# External_Flash.net
KiCad netlist of a schematic drawn in Altium Designer
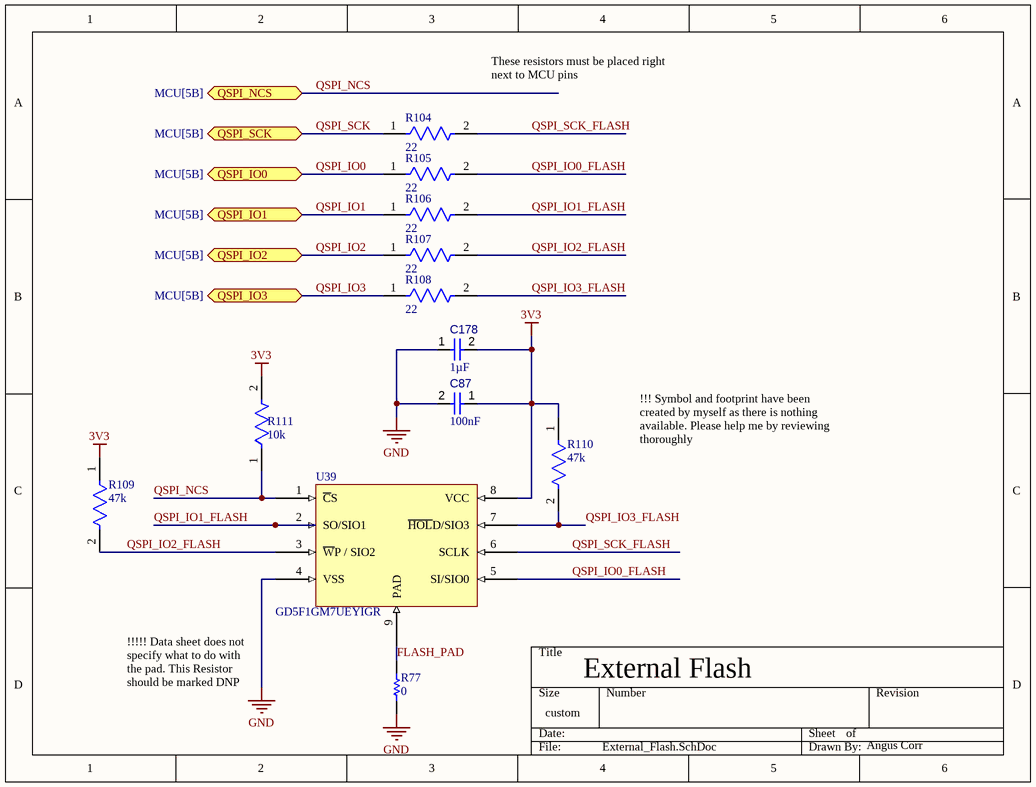
[diagram p0:  External_Flash.SchDoc]

(export (version "E")
  (design (tool "Eeschema 10.0.6"))
  (components
    (comp (ref "C87")
      (value "100nF")
      (footprint "CAPC1608X90X40NL10T20")
      (description "Chip Capacitor, 100 nF, +/- 10%, 50 V, 0603 (1608 Metric)")
      (fields (field (name "TOLERANCE") "10%") (field (name "Comment") "Capacitor 100 nF +/-10% 50 V 0603"))
      (libsource (lib "HIL RIG FYP") (part "CAP-NP-2"))
    )
    (comp (ref "C178")
      (value "1µF")
      (footprint "CAPC1608X90X40LL10T20")
      (description "Chip Capacitor, 1 uF, +/- 10%, 25 V, 0603 (1608 Metric)")
      (fields (field (name "TOLERANCE") "10%") (field (name "Comment") "Capacitor 1 uF +/- 10% 25 V 0603"))
      (libsource (lib "HIL RIG FYP") (part "CAP-NP-2"))
    )
    (comp (ref "R77")
      (value "0")
      (footprint "RESC1608X55X25ML10T15")
      (description "Chip Resistor, 0 Ohm, 0.1 W, -55 to 155 degC, 0603 (1608 Metric)")
      (fields (field (name "POWER") "100mW") (field (name "TOLERANCE") "5%"))
      (libsource (lib "HIL RIG FYP") (part "RES-2"))
    )
    (comp (ref "R104")
      (value "22")
      (footprint "FP-RC0603-0_55-IPC_A")
      (description "100mW Thick Film Resistors 75V ±100ppm/℃ ±5% 22Ω 0603 Chip Resistor - Surface Mount ROHS")
      (fields (field (name "TOLERANCE") "5%") (field (name "Comment") "RC0603JR-0722RL"))
      (libsource (lib "HIL RIG FYP") (part "1029c3af85768c4190bb7ad29bc67b5"))
    )
    (comp (ref "R105")
      (value "22")
      (footprint "FP-RC0603-0_55-IPC_A")
      (description "100mW Thick Film Resistors 75V ±100ppm/℃ ±5% 22Ω 0603 Chip Resistor - Surface Mount ROHS")
      (fields (field (name "TOLERANCE") "5%") (field (name "Comment") "RC0603JR-0722RL"))
      (libsource (lib "HIL RIG FYP") (part "1029c3af85768c4190bb7ad29bc67b5"))
    )
    (comp (ref "R106")
      (value "22")
      (footprint "FP-RC0603-0_55-IPC_A")
      (description "100mW Thick Film Resistors 75V ±100ppm/℃ ±5% 22Ω 0603 Chip Resistor - Surface Mount ROHS")
      (fields (field (name "TOLERANCE") "5%") (field (name "Comment") "RC0603JR-0722RL"))
      (libsource (lib "HIL RIG FYP") (part "1029c3af85768c4190bb7ad29bc67b5"))
    )
    (comp (ref "R107")
      (value "22")
      (footprint "FP-RC0603-0_55-IPC_A")
      (description "100mW Thick Film Resistors 75V ±100ppm/℃ ±5% 22Ω 0603 Chip Resistor - Surface Mount ROHS")
      (fields (field (name "TOLERANCE") "5%") (field (name "Comment") "RC0603JR-0722RL"))
      (libsource (lib "HIL RIG FYP") (part "1029c3af85768c4190bb7ad29bc67b5"))
    )
    (comp (ref "R108")
      (value "22")
      (footprint "FP-RC0603-0_55-IPC_A")
      (description "100mW Thick Film Resistors 75V ±100ppm/℃ ±5% 22Ω 0603 Chip Resistor - Surface Mount ROHS")
      (fields (field (name "TOLERANCE") "5%") (field (name "Comment") "RC0603JR-0722RL"))
      (libsource (lib "HIL RIG FYP") (part "1029c3af85768c4190bb7ad29bc67b5"))
    )
    (comp (ref "R109")
      (value "47k")
      (footprint "FP-AC0603-IPC_A")
      (fields (field (name "TOLERANCE") "0.5%") (field (name "Comment") "AC0603DR-0747KL"))
      (libsource (lib "HIL RIG FYP") (part "1029c3af85768c4190bb7ad29bc67b5"))
    )
    (comp (ref "R110")
      (value "47k")
      (footprint "FP-AC0603-IPC_A")
      (fields (field (name "TOLERANCE") "0.5%") (field (name "Comment") "AC0603DR-0747KL"))
      (libsource (lib "HIL RIG FYP") (part "1029c3af85768c4190bb7ad29bc67b5"))
    )
    (comp (ref "R111")
      (value "10k")
      (footprint "FP-RT0603-IPC_A")
      (description "Res Thin Film 0603 10K Ohm 0.1% 1/10W ¦25ppm/¦C SMD Paper T/R")
      (fields (field (name "TOLERANCE") "0.1%") (field (name "Comment") "RT0603BRD0710KL"))
      (libsource (lib "HIL RIG FYP") (part "1029c3af85768c4190bb7ad29bc67b5"))
    )
    (comp (ref "U39")
      (value "GD5F1GM7UEYIGR")
      (footprint "PSON127P800X80_HS-9M")
      (description "Spi Nand Flash (with Ecc), 1GBIT,")
      (libsource (lib "HIL RIG FYP") (part "GD5F1GM7UEYIGR-Symbol-1"))
    )
  )
  (nets
    (net (code "1") (name "/FLASH_PAD") (class "Default")
      (node (ref "R77") (pin "1") (pinfunction "1_1") (pintype "passive"))
      (node (ref "U39") (pin "9") (pinfunction "PAD_9") (pintype "input"))
    )
    (net (code "2") (name "/QSPI_IO0") (class "Default")
      (node (ref "R105") (pin "1") (pinfunction "1_1") (pintype "passive"))
    )
    (net (code "3") (name "/QSPI_IO0_FLASH") (class "Default")
      (node (ref "R105") (pin "2") (pinfunction "2_2") (pintype "passive"))
      (node (ref "U39") (pin "5") (pinfunction "SI/SIO0_5") (pintype "input"))
    )
    (net (code "4") (name "/QSPI_IO1") (class "Default")
      (node (ref "R106") (pin "1") (pinfunction "1_1") (pintype "passive"))
    )
    (net (code "5") (name "/QSPI_IO1_FLASH") (class "Default")
      (node (ref "R106") (pin "2") (pinfunction "2_2") (pintype "passive"))
      (node (ref "U39") (pin "2") (pinfunction "SO/SIO1_2") (pintype "input"))
    )
    (net (code "6") (name "/QSPI_IO2") (class "Default")
      (node (ref "R107") (pin "1") (pinfunction "1_1") (pintype "passive"))
    )
    (net (code "7") (name "/QSPI_IO2_FLASH") (class "Default")
      (node (ref "R107") (pin "2") (pinfunction "2_2") (pintype "passive"))
      (node (ref "R109") (pin "2") (pinfunction "2_2") (pintype "passive"))
      (node (ref "U39") (pin "3") (pinfunction "~{W}P_/_SIO2_3") (pintype "input"))
    )
    (net (code "8") (name "/QSPI_IO3") (class "Default")
      (node (ref "R108") (pin "1") (pinfunction "1_1") (pintype "passive"))
    )
    (net (code "9") (name "/QSPI_IO3_FLASH") (class "Default")
      (node (ref "R108") (pin "2") (pinfunction "2_2") (pintype "passive"))
      (node (ref "R110") (pin "2") (pinfunction "2_2") (pintype "passive"))
      (node (ref "U39") (pin "7") (pinfunction "~{HOL}D/SIO3_7") (pintype "input"))
    )
    (net (code "10") (name "/QSPI_NCS") (class "Default")
      (node (ref "R111") (pin "1") (pinfunction "1_1") (pintype "passive"))
      (node (ref "U39") (pin "1") (pinfunction "~{C}S_1") (pintype "input"))
    )
    (net (code "11") (name "/QSPI_SCK") (class "Default")
      (node (ref "R104") (pin "1") (pinfunction "1_1") (pintype "passive"))
    )
    (net (code "12") (name "/QSPI_SCK_FLASH") (class "Default")
      (node (ref "R104") (pin "2") (pinfunction "2_2") (pintype "passive"))
      (node (ref "U39") (pin "6") (pinfunction "SCLK_6") (pintype "input"))
    )
    (net (code "13") (name "3V3") (class "Default")
      (node (ref "C178") (pin "2") (pinfunction "2_2") (pintype "passive"))
      (node (ref "C87") (pin "1") (pinfunction "1_1") (pintype "passive"))
      (node (ref "R109") (pin "1") (pinfunction "1_1") (pintype "passive"))
      (node (ref "R110") (pin "1") (pinfunction "1_1") (pintype "passive"))
      (node (ref "R111") (pin "2") (pinfunction "2_2") (pintype "passive"))
      (node (ref "U39") (pin "8") (pinfunction "VCC_8") (pintype "input"))
    )
    (net (code "14") (name "GND") (class "Default")
      (node (ref "C178") (pin "1") (pinfunction "1_1") (pintype "passive"))
      (node (ref "C87") (pin "2") (pinfunction "2_2") (pintype "passive"))
      (node (ref "R77") (pin "2") (pinfunction "2_2") (pintype "passive"))
      (node (ref "U39") (pin "4") (pinfunction "VSS_4") (pintype "input"))
    )
  )
)
